# 02_POWER.net
KiCad netlist of a schematic drawn in Altium Designer
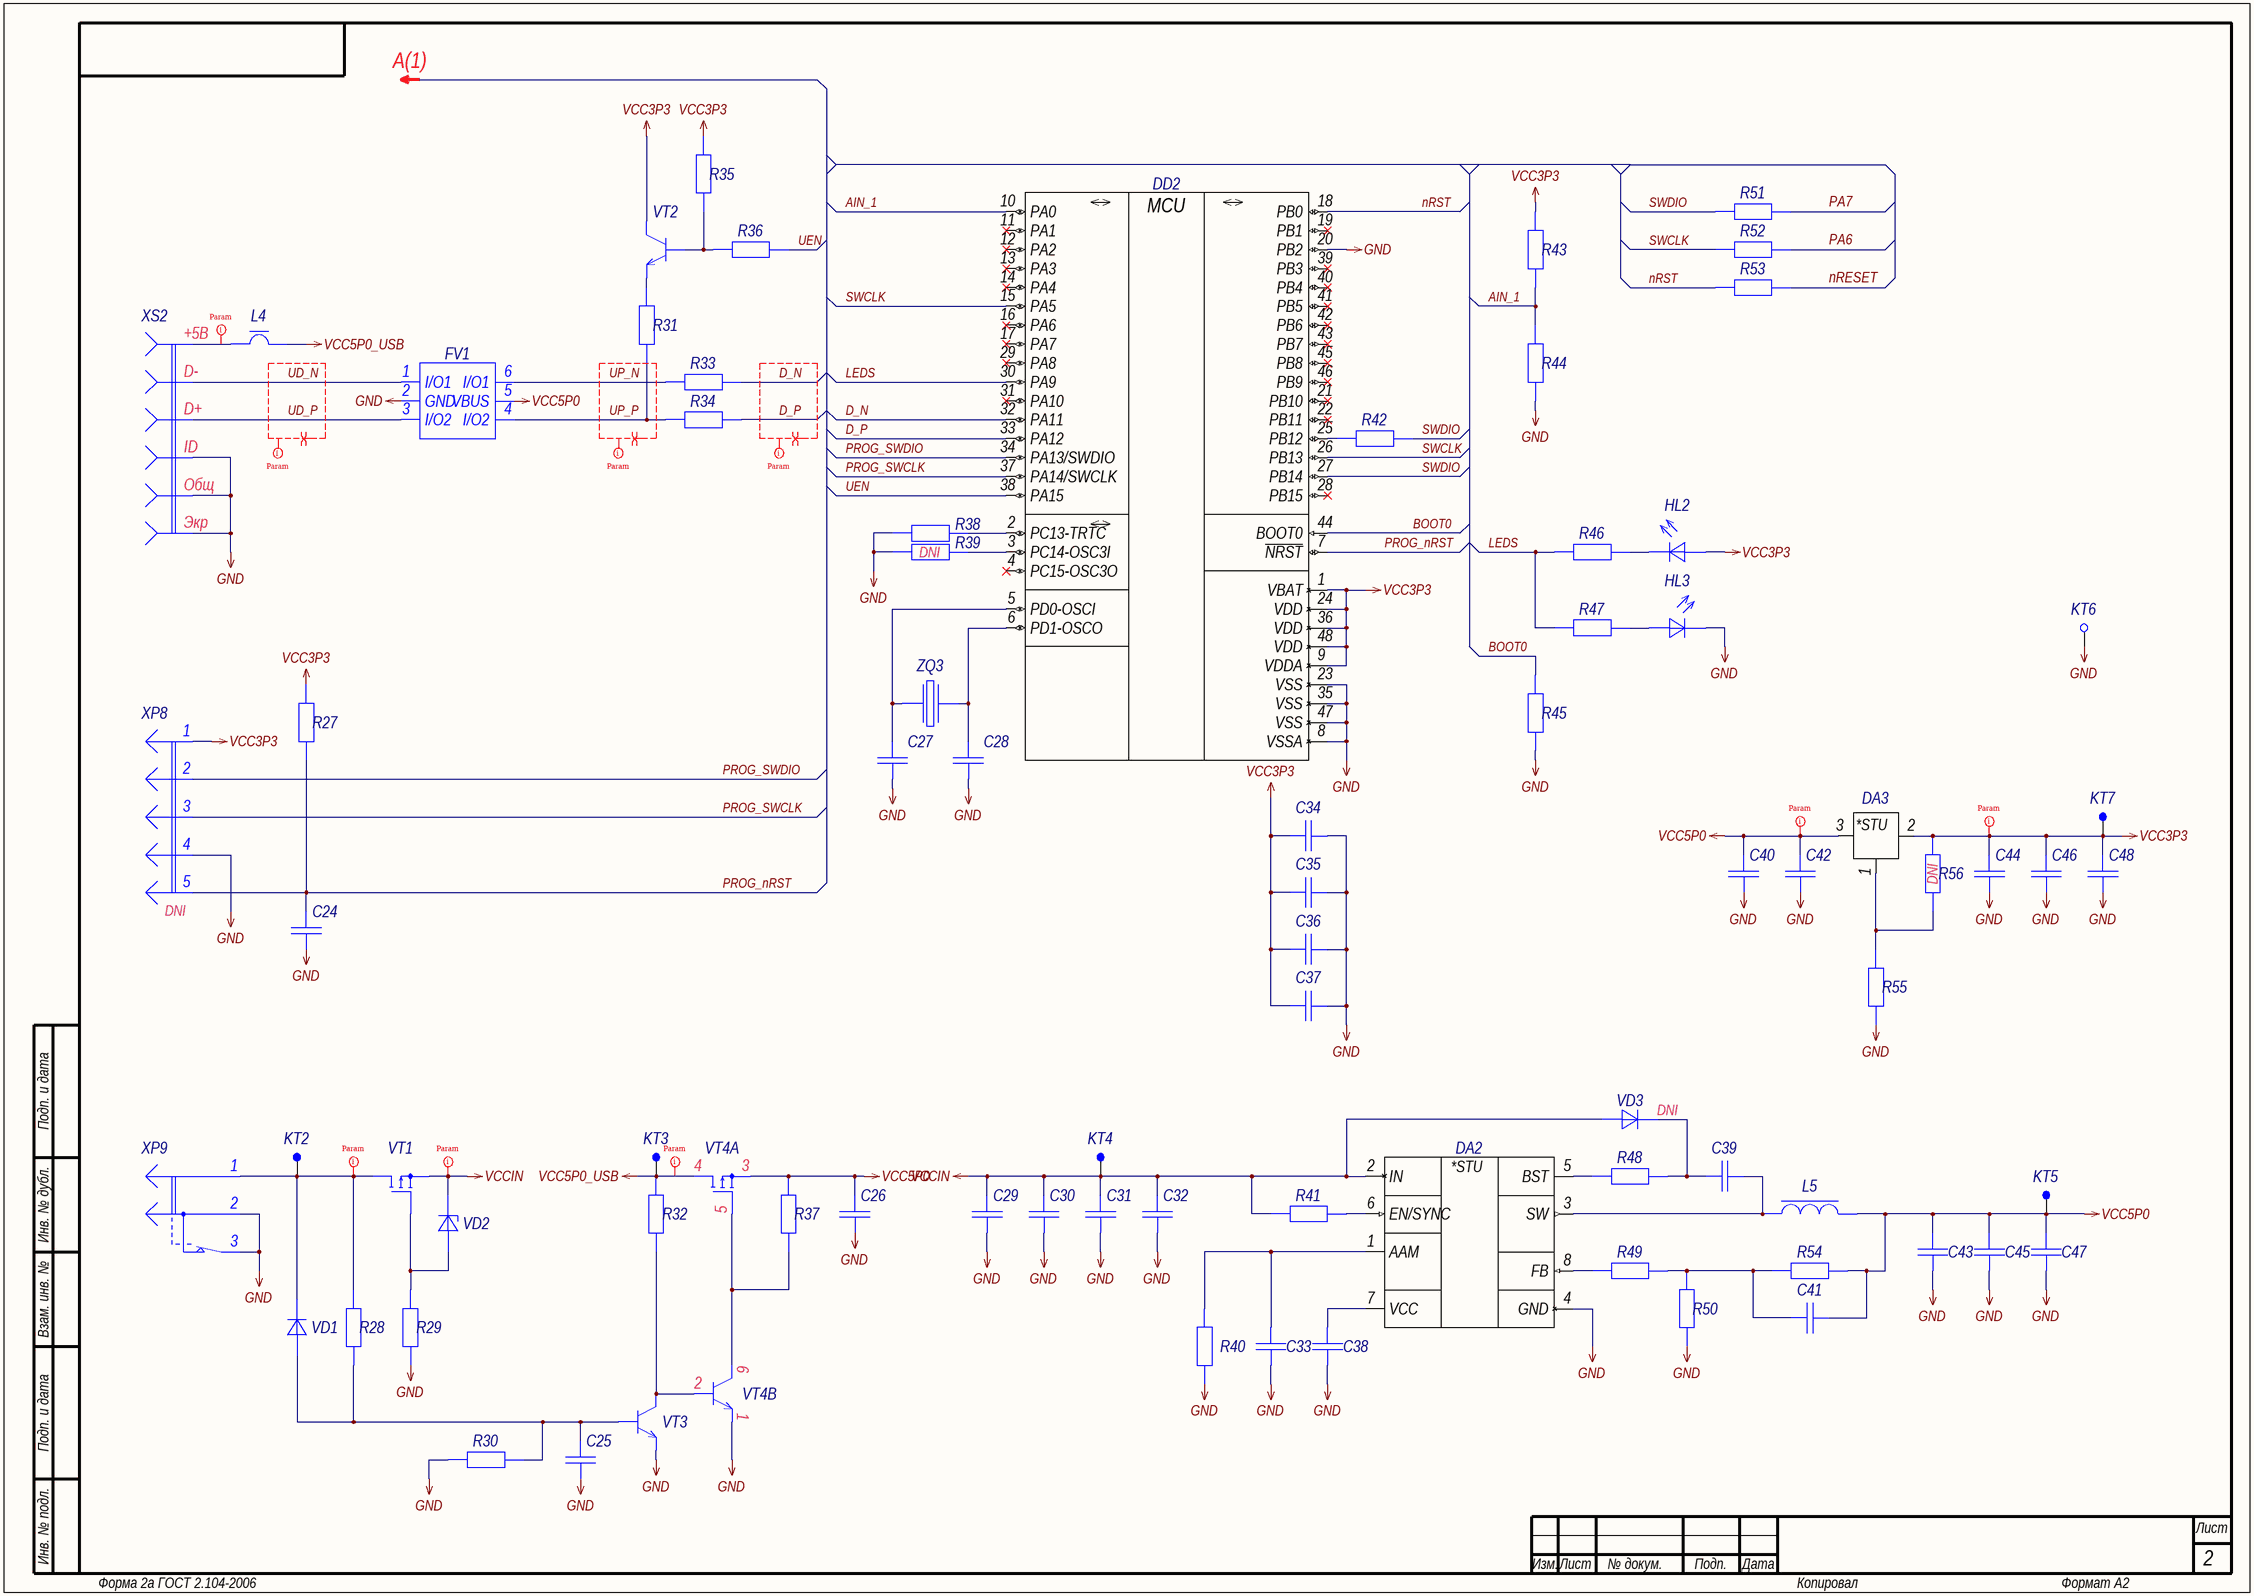
[diagram p0: 02_POWER.SchDoc]

(export (version "E")
  (design (tool "Eeschema 10.0.6"))
  (components
    (comp (ref "C24")
      (value "Capacitor")
      (footprint "C0603_L")
      (fields
        (field (name "PART NUMBER") "GRM188R72A104KA35D")
        (field (name "VOLTAGE") "100V")
        (field (name "TOLERANCE") "±10%")
        (field (name "PUBLISHER") "Andrew Danich")
      )
      (libsource (lib "ADLib") (part "Capacitor"))
    )
    (comp (ref "C25")
      (value "Capacitor")
      (footprint "C0603_L")
      (fields
        (field (name "PART NUMBER") "GRM188R72A104KA35D")
        (field (name "VOLTAGE") "100V")
        (field (name "TOLERANCE") "±10%")
        (field (name "PUBLISHER") "Andrew Danich")
      )
      (libsource (lib "ADLib") (part "Capacitor"))
    )
    (comp (ref "C26")
      (value "Capacitor")
      (footprint "C0805_L")
      (fields
        (field (name "PART NUMBER") "GRM21BR60J226ME39L")
        (field (name "VOLTAGE") "6.3V")
        (field (name "TOLERANCE") "±20%")
        (field (name "PUBLISHER") "Andrew Danich")
      )
      (libsource (lib "ADLib") (part "Capacitor"))
    )
    (comp (ref "C27")
      (value "Capacitor")
      (footprint "C0603_L")
      (fields
        (field (name "PART NUMBER") "GCM1885C1H150JA16D")
        (field (name "VOLTAGE") "50V")
        (field (name "TOLERANCE") "±5%")
        (field (name "PUBLISHER") "Andrew Danich")
      )
      (libsource (lib "ADLib") (part "Capacitor"))
    )
    (comp (ref "C28")
      (value "Capacitor")
      (footprint "C0603_L")
      (fields
        (field (name "PART NUMBER") "GCM1885C1H150JA16D")
        (field (name "VOLTAGE") "50V")
        (field (name "TOLERANCE") "±5%")
        (field (name "PUBLISHER") "Andrew Danich")
      )
      (libsource (lib "ADLib") (part "Capacitor"))
    )
    (comp (ref "C29")
      (value "Capacitor")
      (footprint "C1206_L")
      (fields
        (field (name "PART NUMBER") "GRM31CR71A226KE15L")
        (field (name "VOLTAGE") "10V")
        (field (name "TOLERANCE") "±10%")
        (field (name "PUBLISHER") "Andrew Danich")
      )
      (libsource (lib "ADLib") (part "Capacitor"))
    )
    (comp (ref "C30")
      (value "Capacitor")
      (footprint "C1206_L")
      (fields
        (field (name "PART NUMBER") "GRM31CR71A226KE15L")
        (field (name "VOLTAGE") "10V")
        (field (name "TOLERANCE") "±10%")
        (field (name "PUBLISHER") "Andrew Danich")
      )
      (libsource (lib "ADLib") (part "Capacitor"))
    )
    (comp (ref "C31")
      (value "Capacitor")
      (footprint "C1206_L")
      (fields
        (field (name "PART NUMBER") "GRM31CR71A226KE15L")
        (field (name "VOLTAGE") "10V")
        (field (name "TOLERANCE") "±10%")
        (field (name "PUBLISHER") "Andrew Danich")
      )
      (libsource (lib "ADLib") (part "Capacitor"))
    )
    (comp (ref "C32")
      (value "Capacitor")
      (footprint "C0603_L")
      (fields
        (field (name "PART NUMBER") "GRM188R72A104KA35D")
        (field (name "VOLTAGE") "100V")
        (field (name "TOLERANCE") "±10%")
        (field (name "PUBLISHER") "Andrew Danich")
      )
      (libsource (lib "ADLib") (part "Capacitor"))
    )
    (comp (ref "C33")
      (value "Capacitor")
      (footprint "C0603_L")
      (fields
        (field (name "PART NUMBER") "GRM1885C2A102JA01D")
        (field (name "VOLTAGE") "100V")
        (field (name "TOLERANCE") "±5%")
        (field (name "PUBLISHER") "Andrew Danich")
      )
      (libsource (lib "ADLib") (part "Capacitor"))
    )
    (comp (ref "C34")
      (value "Capacitor")
      (footprint "C0603_L")
      (fields
        (field (name "PART NUMBER") "GRM188R72A104KA35D")
        (field (name "VOLTAGE") "100V")
        (field (name "TOLERANCE") "±10%")
        (field (name "PUBLISHER") "Andrew Danich")
      )
      (libsource (lib "ADLib") (part "Capacitor"))
    )
    (comp (ref "C35")
      (value "Capacitor")
      (footprint "C0603_L")
      (fields
        (field (name "PART NUMBER") "GRM188R72A104KA35D")
        (field (name "VOLTAGE") "100V")
        (field (name "TOLERANCE") "±10%")
        (field (name "PUBLISHER") "Andrew Danich")
      )
      (libsource (lib "ADLib") (part "Capacitor"))
    )
    (comp (ref "C36")
      (value "Capacitor")
      (footprint "C0603_L")
      (fields
        (field (name "PART NUMBER") "GRM188R72A104KA35D")
        (field (name "VOLTAGE") "100V")
        (field (name "TOLERANCE") "±10%")
        (field (name "PUBLISHER") "Andrew Danich")
      )
      (libsource (lib "ADLib") (part "Capacitor"))
    )
    (comp (ref "C37")
      (value "Capacitor")
      (footprint "C0603_L")
      (fields
        (field (name "PART NUMBER") "GRM188R72A104KA35D")
        (field (name "VOLTAGE") "100V")
        (field (name "TOLERANCE") "±10%")
        (field (name "PUBLISHER") "Andrew Danich")
      )
      (libsource (lib "ADLib") (part "Capacitor"))
    )
    (comp (ref "C38")
      (value "Capacitor")
      (footprint "C0603_L")
      (fields
        (field (name "PART NUMBER") "GRM188R72A104KA35D")
        (field (name "VOLTAGE") "100V")
        (field (name "TOLERANCE") "±10%")
        (field (name "PUBLISHER") "Andrew Danich")
      )
      (libsource (lib "ADLib") (part "Capacitor"))
    )
    (comp (ref "C39")
      (value "Capacitor")
      (footprint "C0603_L")
      (fields
        (field (name "PART NUMBER") "GRM188R72A104KA35D")
        (field (name "VOLTAGE") "100V")
        (field (name "TOLERANCE") "±10%")
        (field (name "PUBLISHER") "Andrew Danich")
      )
      (libsource (lib "ADLib") (part "Capacitor"))
    )
    (comp (ref "C40")
      (value "Capacitor")
      (footprint "C0805_L")
      (fields
        (field (name "PART NUMBER") "GRM21BR60J226ME39L")
        (field (name "VOLTAGE") "6.3V")
        (field (name "TOLERANCE") "±20%")
        (field (name "PUBLISHER") "Andrew Danich")
      )
      (libsource (lib "ADLib") (part "Capacitor"))
    )
    (comp (ref "C41")
      (value "Capacitor")
      (footprint "C0603_L")
      (fields
        (field (name "PART NUMBER") "GRM1885C1H330JA01D")
        (field (name "VOLTAGE") "50V")
        (field (name "TOLERANCE") "±5%")
        (field (name "PUBLISHER") "Andrew Danich")
      )
      (libsource (lib "ADLib") (part "Capacitor"))
    )
    (comp (ref "C42")
      (value "Capacitor")
      (footprint "C0603_L")
      (fields
        (field (name "PART NUMBER") "GRM188R72A104KA35D")
        (field (name "VOLTAGE") "100V")
        (field (name "TOLERANCE") "±10%")
        (field (name "PUBLISHER") "Andrew Danich")
      )
      (libsource (lib "ADLib") (part "Capacitor"))
    )
    (comp (ref "C43")
      (value "Capacitor")
      (footprint "C0805_L")
      (fields
        (field (name "PART NUMBER") "GRM21BR60J226ME39L")
        (field (name "VOLTAGE") "6.3V")
        (field (name "TOLERANCE") "±20%")
        (field (name "PUBLISHER") "Andrew Danich")
      )
      (libsource (lib "ADLib") (part "Capacitor"))
    )
    (comp (ref "C44")
      (value "Capacitor")
      (footprint "C0603_L")
      (fields
        (field (name "PART NUMBER") "GRM188R72A104KA35D")
        (field (name "VOLTAGE") "100V")
        (field (name "TOLERANCE") "±10%")
        (field (name "PUBLISHER") "Andrew Danich")
      )
      (libsource (lib "ADLib") (part "Capacitor"))
    )
    (comp (ref "C45")
      (value "Capacitor")
      (footprint "C0805_L")
      (fields
        (field (name "PART NUMBER") "GRM21BR60J226ME39L")
        (field (name "VOLTAGE") "6.3V")
        (field (name "TOLERANCE") "±20%")
        (field (name "PUBLISHER") "Andrew Danich")
      )
      (libsource (lib "ADLib") (part "Capacitor"))
    )
    (comp (ref "C46")
      (value "Capacitor")
      (footprint "C0805_L")
      (fields
        (field (name "PART NUMBER") "GRM21BR60J226ME39L")
        (field (name "VOLTAGE") "6.3V")
        (field (name "TOLERANCE") "±20%")
        (field (name "PUBLISHER") "Andrew Danich")
      )
      (libsource (lib "ADLib") (part "Capacitor"))
    )
    (comp (ref "C47")
      (value "Capacitor")
      (footprint "C0805_L")
      (fields
        (field (name "PART NUMBER") "GRM21BR60J226ME39L")
        (field (name "VOLTAGE") "6.3V")
        (field (name "TOLERANCE") "±20%")
        (field (name "PUBLISHER") "Andrew Danich")
      )
      (libsource (lib "ADLib") (part "Capacitor"))
    )
    (comp (ref "C48")
      (value "Capacitor")
      (footprint "C0805_L")
      (fields
        (field (name "PART NUMBER") "GRM21BR60J226ME39L")
        (field (name "VOLTAGE") "6.3V")
        (field (name "TOLERANCE") "±20%")
        (field (name "PUBLISHER") "Andrew Danich")
      )
      (libsource (lib "ADLib") (part "Capacitor"))
    )
    (comp (ref "DA2")
      (value "MP2315GJ")
      (footprint "TSOT-23-8_065P290X160X100_N")
      (fields
        (field (name "PART NUMBER") "MP2315GJ-Z")
        (field (name "MANUFACTURER") "Monolithic Power Systems")
        (field (name "PUBLISHER") "Andrew Danich")
      )
      (libsource (lib "ADLib") (part "MP2315GJ"))
    )
    (comp (ref "DA3")
      (value "LM1117-Series")
      (footprint "SOT-223_230P650X350X180_N")
      (fields (field (name "PART NUMBER") "LM1117MPX-3.3") (field (name "PUBLISHER") "Andrew Danich"))
      (libsource (lib "ADLib") (part "LM1117-Series"))
    )
    (comp (ref "DD2")
      (value "STM32F103Cxxx-Series")
      (footprint "LQFP-48_050P700X700X160_N")
      (fields
        (field (name "PART NUMBER") "STM32F103C8T6")
        (field (name "MANUFACTURER") "STMicroelectronics")
        (field (name "PUBLISHER") "Andrew Danich")
      )
      (libsource (lib "ADLib") (part "STM32F103Cxxx-Series"))
    )
    (comp (ref "FV1")
      (value "USBLC6-2SC6")
      (footprint "SOT-23-6_095P290X160X145_N")
      (fields (field (name "MANUFACTURER") "STMicroelectronics") (field (name "PUBLISHER") "Andrew Danich"))
      (libsource (lib "ADLib") (part "USBLC6-2SC6"))
    )
    (comp (ref "HL2")
      (value "Text")
      (footprint "LD0603_L")
      (fields (field (name "PART NUMBER") "BL-LS0603GC") (field (name "PUBLISHER") "Andrew Danich"))
      (libsource (lib "ADLib") (part "Led-1"))
    )
    (comp (ref "HL3")
      (value "Text")
      (footprint "LD0603_L")
      (fields (field (name "PART NUMBER") "BL-LS0603HC") (field (name "PUBLISHER") "Andrew Danich"))
      (libsource (lib "ADLib") (part "Led-1"))
    )
    (comp (ref "KT2")
      (value "VCCIN")
      (footprint "TP-SMT-C-0.8mm")
      (fields (field (name "PART NUMBER") "TestPoint-SMT") (field (name "PUBLISHER") "Andrew Danich"))
      (libsource (lib "ADLib") (part "TP-S-1"))
    )
    (comp (ref "KT3")
      (value "VBUS")
      (footprint "TP-SMT-C-0.8mm")
      (fields (field (name "PART NUMBER") "TestPoint-SMT") (field (name "PUBLISHER") "Andrew Danich"))
      (libsource (lib "ADLib") (part "TP-S-1"))
    )
    (comp (ref "KT4")
      (value "VCCIN")
      (footprint "TP-SMT-C-0.8mm")
      (fields (field (name "PART NUMBER") "TestPoint-SMT") (field (name "PUBLISHER") "Andrew Danich"))
      (libsource (lib "ADLib") (part "TP-S-1"))
    )
    (comp (ref "KT5")
      (value "+5V")
      (footprint "TP-SMT-C-0.8mm")
      (fields (field (name "PART NUMBER") "TestPoint-SMT") (field (name "PUBLISHER") "Andrew Danich"))
      (libsource (lib "ADLib") (part "TP-S-1"))
    )
    (comp (ref "KT6")
      (value "ОБЩ")
      (footprint "5001")
      (fields
        (field (name "PART NUMBER") "5001")
        (field (name "MANUFACTURER") "Keystone Electronics")
        (field (name "PUBLISHER") "Andrew Danich")
      )
      (libsource (lib "ADLib") (part "TP-1"))
    )
    (comp (ref "KT7")
      (value "+3.3V")
      (footprint "TP-SMT-C-0.8mm")
      (fields (field (name "PART NUMBER") "TestPoint-SMT") (field (name "PUBLISHER") "Andrew Danich"))
      (libsource (lib "ADLib") (part "TP-S-1"))
    )
    (comp (ref "L4")
      (value "FerriteBead")
      (footprint "L0603_L")
      (fields
        (field (name "PART NUMBER") "BLM18PG331SN1")
        (field (name "TOLERANCE") "±25%")
        (field (name "MANUFACTURER") "Murata")
        (field (name "PUBLISHER") "Andrew Danich")
      )
      (libsource (lib "ADLib") (part "FerriteBead"))
    )
    (comp (ref "L5")
      (value "Coil")
      (footprint "SRP5030T-Series")
      (fields
        (field (name "PART NUMBER") "SRP5030T-4R7M")
        (field (name "TOLERANCE") "±20%")
        (field (name "MANUFACTURER") "Bourns")
        (field (name "PUBLISHER") "Andrew Danich")
      )
      (libsource (lib "ADLib") (part "Coil"))
    )
    (comp (ref "R27")
      (value "Resistor")
      (footprint "R0603_L")
      (fields
        (field (name "PART NUMBER") "RC0603JR-0710KL")
        (field (name "TOLERANCE") "±5%")
        (field (name "MANUFACTURER") "Yageo")
        (field (name "PUBLISHER") "Andrew Danich")
      )
      (libsource (lib "ADLib") (part "Resistor"))
    )
    (comp (ref "R28")
      (value "Resistor")
      (footprint "R0603_L")
      (fields
        (field (name "PART NUMBER") "RC0603JR-0710KL")
        (field (name "TOLERANCE") "±5%")
        (field (name "MANUFACTURER") "Yageo")
        (field (name "PUBLISHER") "Andrew Danich")
      )
      (libsource (lib "ADLib") (part "Resistor"))
    )
    (comp (ref "R29")
      (value "Resistor")
      (footprint "R0603_L")
      (fields
        (field (name "PART NUMBER") "RC0603JR-0710KL")
        (field (name "TOLERANCE") "±5%")
        (field (name "MANUFACTURER") "Yageo")
        (field (name "PUBLISHER") "Andrew Danich")
      )
      (libsource (lib "ADLib") (part "Resistor"))
    )
    (comp (ref "R30")
      (value "Resistor")
      (footprint "R0603_L")
      (fields
        (field (name "PART NUMBER") "RC0603JR-0710KL")
        (field (name "TOLERANCE") "±5%")
        (field (name "MANUFACTURER") "Yageo")
        (field (name "PUBLISHER") "Andrew Danich")
      )
      (libsource (lib "ADLib") (part "Resistor"))
    )
    (comp (ref "R31")
      (value "Resistor")
      (footprint "R0603_L")
      (fields
        (field (name "PART NUMBER") "RC0603JR-071K5L")
        (field (name "TOLERANCE") "±5%")
        (field (name "MANUFACTURER") "Yageo")
        (field (name "PUBLISHER") "Andrew Danich")
      )
      (libsource (lib "ADLib") (part "Resistor"))
    )
    (comp (ref "R32")
      (value "Resistor")
      (footprint "R0603_L")
      (fields
        (field (name "PART NUMBER") "RC0603JR-0710KL")
        (field (name "TOLERANCE") "±5%")
        (field (name "MANUFACTURER") "Yageo")
        (field (name "PUBLISHER") "Andrew Danich")
      )
      (libsource (lib "ADLib") (part "Resistor"))
    )
    (comp (ref "R33")
      (value "Resistor")
      (footprint "R0603_L")
      (fields
        (field (name "PART NUMBER") "RC0603JR-0722RL")
        (field (name "TOLERANCE") "±5%")
        (field (name "MANUFACTURER") "Yageo")
        (field (name "PUBLISHER") "Andrew Danich")
      )
      (libsource (lib "ADLib") (part "Resistor"))
    )
    (comp (ref "R34")
      (value "Resistor")
      (footprint "R0603_L")
      (fields
        (field (name "PART NUMBER") "RC0603JR-0722RL")
        (field (name "TOLERANCE") "±5%")
        (field (name "MANUFACTURER") "Yageo")
        (field (name "PUBLISHER") "Andrew Danich")
      )
      (libsource (lib "ADLib") (part "Resistor"))
    )
    (comp (ref "R35")
      (value "Resistor")
      (footprint "R0603_L")
      (fields
        (field (name "PART NUMBER") "RC0603JR-074K7L")
        (field (name "TOLERANCE") "±5%")
        (field (name "MANUFACTURER") "Yageo")
        (field (name "PUBLISHER") "Andrew Danich")
      )
      (libsource (lib "ADLib") (part "Resistor"))
    )
    (comp (ref "R36")
      (value "Resistor")
      (footprint "R0603_L")
      (fields
        (field (name "PART NUMBER") "RC0603JR-07100R")
        (field (name "TOLERANCE") "±5%")
        (field (name "MANUFACTURER") "Yageo")
        (field (name "PUBLISHER") "Andrew Danich")
      )
      (libsource (lib "ADLib") (part "Resistor"))
    )
    (comp (ref "R37")
      (value "Resistor")
      (footprint "R0603_L")
      (fields
        (field (name "PART NUMBER") "RC0603JR-0710KL")
        (field (name "TOLERANCE") "±5%")
        (field (name "MANUFACTURER") "Yageo")
        (field (name "PUBLISHER") "Andrew Danich")
      )
      (libsource (lib "ADLib") (part "Resistor"))
    )
    (comp (ref "R38")
      (value "Resistor")
      (footprint "R0603_L")
      (fields
        (field (name "PART NUMBER") "RC0603JR-0710KL")
        (field (name "TOLERANCE") "±5%")
        (field (name "MANUFACTURER") "Yageo")
        (field (name "PUBLISHER") "Andrew Danich")
      )
      (libsource (lib "ADLib") (part "Resistor"))
    )
    (comp (ref "R39")
      (value "Resistor")
      (footprint "R0603_L")
      (fields
        (field (name "PART NUMBER") "RC0603JR-0710KL")
        (field (name "TOLERANCE") "±5%")
        (field (name "MANUFACTURER") "Yageo")
        (field (name "PUBLISHER") "Andrew Danich")
      )
      (libsource (lib "ADLib") (part "Resistor"))
    )
    (comp (ref "R40")
      (value "Resistor")
      (footprint "R0603_L")
      (fields
        (field (name "PART NUMBER") "RC0603FR-0763K4L")
        (field (name "TOLERANCE") "±1%")
        (field (name "MANUFACTURER") "Yageo")
        (field (name "PUBLISHER") "Andrew Danich")
      )
      (libsource (lib "ADLib") (part "Resistor"))
    )
    (comp (ref "R41")
      (value "Resistor")
      (footprint "R0603_L")
      (fields
        (field (name "PART NUMBER") "RC0603JR-07100KL")
        (field (name "TOLERANCE") "±5%")
        (field (name "MANUFACTURER") "Yageo")
        (field (name "PUBLISHER") "Andrew Danich")
      )
      (libsource (lib "ADLib") (part "Resistor"))
    )
    (comp (ref "R42")
      (value "Resistor")
      (footprint "R0603_L")
      (fields
        (field (name "PART NUMBER") "RC0603JR-07100R")
        (field (name "TOLERANCE") "±5%")
        (field (name "MANUFACTURER") "Yageo")
        (field (name "PUBLISHER") "Andrew Danich")
      )
      (libsource (lib "ADLib") (part "Resistor"))
    )
    (comp (ref "R43")
      (value "Resistor")
      (footprint "R0603_L")
      (fields
        (field (name "PART NUMBER") "RC0603JR-074K7L")
        (field (name "TOLERANCE") "±5%")
        (field (name "MANUFACTURER") "Yageo")
        (field (name "PUBLISHER") "Andrew Danich")
      )
      (libsource (lib "ADLib") (part "Resistor"))
    )
    (comp (ref "R44")
      (value "Resistor")
      (footprint "R0603_L")
      (fields
        (field (name "PART NUMBER") "RC0603JR-074K7L")
        (field (name "TOLERANCE") "±5%")
        (field (name "MANUFACTURER") "Yageo")
        (field (name "PUBLISHER") "Andrew Danich")
      )
      (libsource (lib "ADLib") (part "Resistor"))
    )
    (comp (ref "R45")
      (value "Resistor")
      (footprint "R0603_L")
      (fields
        (field (name "PART NUMBER") "RC0603JR-0710KL")
        (field (name "TOLERANCE") "±5%")
        (field (name "MANUFACTURER") "Yageo")
        (field (name "PUBLISHER") "Andrew Danich")
      )
      (libsource (lib "ADLib") (part "Resistor"))
    )
    (comp (ref "R46")
      (value "Resistor")
      (footprint "R0603_L")
      (fields
        (field (name "PART NUMBER") "RC0603JR-07330RL")
        (field (name "TOLERANCE") "±5%")
        (field (name "MANUFACTURER") "Yageo")
        (field (name "PUBLISHER") "Andrew Danich")
      )
      (libsource (lib "ADLib") (part "Resistor"))
    )
    (comp (ref "R47")
      (value "Resistor")
      (footprint "R0603_L")
      (fields
        (field (name "PART NUMBER") "RC0603JR-07330RL")
        (field (name "TOLERANCE") "±5%")
        (field (name "MANUFACTURER") "Yageo")
        (field (name "PUBLISHER") "Andrew Danich")
      )
      (libsource (lib "ADLib") (part "Resistor"))
    )
    (comp (ref "R48")
      (value "Resistor")
      (footprint "R0603_L")
      (fields
        (field (name "PART NUMBER") "RC0603JR-0720RL")
        (field (name "TOLERANCE") "±5%")
        (field (name "MANUFACTURER") "Yageo")
        (field (name "PUBLISHER") "Andrew Danich")
      )
      (libsource (lib "ADLib") (part "Resistor"))
    )
    (comp (ref "R49")
      (value "Resistor")
      (footprint "R0603_L")
      (fields
        (field (name "PART NUMBER") "RC0603JR-0733KL")
        (field (name "TOLERANCE") "±5%")
        (field (name "MANUFACTURER") "Yageo")
        (field (name "PUBLISHER") "Andrew Danich")
      )
      (libsource (lib "ADLib") (part "Resistor"))
    )
    (comp (ref "R50")
      (value "Resistor")
      (footprint "R0603_L")
      (fields
        (field (name "PART NUMBER") "RC0603JR-076K8L")
        (field (name "TOLERANCE") "±5%")
        (field (name "MANUFACTURER") "Yageo")
        (field (name "PUBLISHER") "Andrew Danich")
      )
      (libsource (lib "ADLib") (part "Resistor"))
    )
    (comp (ref "R51")
      (value "Resistor")
      (footprint "R0603_L")
      (fields
        (field (name "PART NUMBER") "RC0603JR-0722RL")
        (field (name "TOLERANCE") "±5%")
        (field (name "MANUFACTURER") "Yageo")
        (field (name "PUBLISHER") "Andrew Danich")
      )
      (libsource (lib "ADLib") (part "Resistor"))
    )
    (comp (ref "R52")
      (value "Resistor")
      (footprint "R0603_L")
      (fields
        (field (name "PART NUMBER") "RC0603JR-0722RL")
        (field (name "TOLERANCE") "±5%")
        (field (name "MANUFACTURER") "Yageo")
        (field (name "PUBLISHER") "Andrew Danich")
      )
      (libsource (lib "ADLib") (part "Resistor"))
    )
    (comp (ref "R53")
      (value "Resistor")
      (footprint "R0603_L")
      (fields
        (field (name "PART NUMBER") "RC0603JR-0722RL")
        (field (name "TOLERANCE") "±5%")
        (field (name "MANUFACTURER") "Yageo")
        (field (name "PUBLISHER") "Andrew Danich")
      )
      (libsource (lib "ADLib") (part "Resistor"))
    )
    (comp (ref "R54")
      (value "Resistor")
      (footprint "R0603_L")
      (fields
        (field (name "PART NUMBER") "RC0603JR-0736KL")
        (field (name "TOLERANCE") "±5%")
        (field (name "MANUFACTURER") "Yageo")
        (field (name "PUBLISHER") "Andrew Danich")
      )
      (libsource (lib "ADLib") (part "Resistor"))
    )
    (comp (ref "R55")
      (value "Resistor")
      (footprint "R0603_L")
      (fields
        (field (name "PART NUMBER") "RC0603JR-070R")
        (field (name "TOLERANCE") "±5%")
        (field (name "MANUFACTURER") "Yageo")
        (field (name "PUBLISHER") "Andrew Danich")
      )
      (libsource (lib "ADLib") (part "Resistor"))
    )
    (comp (ref "R56")
      (value "Resistor")
      (footprint "R0603_L")
      (fields
        (field (name "PART NUMBER") "RC0603JR-070R")
        (field (name "TOLERANCE") "±5%")
        (field (name "MANUFACTURER") "Yageo")
        (field (name "PUBLISHER") "Andrew Danich")
      )
      (libsource (lib "ADLib") (part "Resistor"))
    )
    (comp (ref "VD1")
      (value "Diode")
      (footprint "SOD-323")
      (fields
        (field (name "PART NUMBER") "1N4148WS-7-F")
        (field (name "MANUFACTURER") "Diodes Incorporated")
        (field (name "PUBLISHER") "Andrew Danich")
      )
      (libsource (lib "ADLib") (part "Diode"))
    )
    (comp (ref "VD2")
      (value "Zener")
      (footprint "SOD-323")
      (fields
        (field (name "PART NUMBER") "BZX384-C12")
        (field (name "MANUFACTURER") "NXP")
        (field (name "PUBLISHER") "Andrew Danich")
      )
      (libsource (lib "ADLib") (part "Zener"))
    )
    (comp (ref "VD3")
      (value "Diode")
      (footprint "SOD-323")
      (fields
        (field (name "PART NUMBER") "1N4148WS-7-F")
        (field (name "MANUFACTURER") "Diodes Incorporated")
        (field (name "PUBLISHER") "Andrew Danich")
      )
      (libsource (lib "ADLib") (part "Diode"))
    )
    (comp (ref "VT1")
      (value "MOSFET-P")
      (footprint "SOT-23_190P290X160X145_N")
      (fields
        (field (name "PART NUMBER") "IRLML9301TRPBF")
        (field (name "MANUFACTURER") "International Rectifier")
        (field (name "PUBLISHER") "Andrew Danich")
      )
      (libsource (lib "ADLib") (part "MOSFET-P"))
    )
    (comp (ref "VT2")
      (value "BJT-NPN")
      (footprint "SOT-23_190P290X160X145_N")
      (fields (field (name "PART NUMBER") "BC847") (field (name "PUBLISHER") "Andrew Danich"))
      (libsource (lib "ADLib") (part "BJT-NPN"))
    )
    (comp (ref "VT3")
      (value "BJT-NPN")
      (footprint "SOT-23_190P290X160X145_N")
      (fields (field (name "PART NUMBER") "BC847") (field (name "PUBLISHER") "Andrew Danich"))
      (libsource (lib "ADLib") (part "BJT-NPN"))
    )
    (comp (ref "VT4")
      (value "PMC85XP")
      (footprint "SOT-1118-2M_065P200X200X065_N")
      (fields (field (name "MANUFACTURER") "NXP Semiconductors") (field (name "PUBLISHER") "Andrew Danich"))
      (libsource (lib "ADLib") (part "PMC85XP"))
    )
    (comp (ref "XP8")
      (value "Prog")
      (footprint "PLS-5")
      (fields (field (name "PART NUMBER") "PLS-5") (field (name "PUBLISHER") "Andrew Danich"))
      (libsource (lib "ADLib") (part "Con-5-M"))
    )
    (comp (ref "XP9")
      (value "DC")
      (footprint "DJK-02-Series")
      (fields
        (field (name "PART NUMBER") "DJK-02A")
        (field (name "MANUFACTURER") "JIA YI")
        (field (name "PUBLISHER") "Andrew Danich")
      )
      (libsource (lib "ADLib") (part "Con-2-M-DP"))
    )
    (comp (ref "XS2")
      (value "J-Link")
      (footprint "1981568-1")
      (fields
        (field (name "PART NUMBER") "1981568-1")
        (field (name "MANUFACTURER") "TE Connectivity")
        (field (name "PUBLISHER") "Andrew Danich")
      )
      (libsource (lib "ADLib") (part "Con-6-F-USB"))
    )
    (comp (ref "ZQ3")
      (value "Crystal")
      (footprint "SMD 5x3.2mm")
      (fields
        (field (name "PART NUMBER") "KX-9A 8.0 MHz 30/50/100 16 pF")
        (field (name "MANUFACTURER") "Geyer")
        (field (name "PUBLISHER") "Andrew Danich")
      )
      (libsource (lib "ADLib") (part "Crystal"))
    )
  )
  (nets
    (net (code "1") (name "/AIN_1") (class "Default")
      (node (ref "DD2") (pin "10") (pinfunction "PA0_10") (pintype "bidirectional"))
      (node (ref "R43") (pin "1") (pinfunction "1_1") (pintype "passive"))
      (node (ref "R44") (pin "2") (pinfunction "2_2") (pintype "passive"))
    )
    (net (code "2") (name "/BOOT0") (class "Default")
      (node (ref "DD2") (pin "44") (pinfunction "BOOT0_44") (pintype "input"))
      (node (ref "R45") (pin "2") (pinfunction "2_2") (pintype "passive"))
    )
    (net (code "3") (name "/D_N") (class "Default")
      (node (ref "DD2") (pin "32") (pinfunction "PA11_32") (pintype "bidirectional"))
      (node (ref "R33") (pin "2") (pinfunction "2_2") (pintype "passive"))
    )
    (net (code "4") (name "/D_P") (class "Default")
      (node (ref "DD2") (pin "33") (pinfunction "PA12_33") (pintype "bidirectional"))
      (node (ref "R34") (pin "2") (pinfunction "2_2") (pintype "passive"))
    )
    (net (code "5") (name "/LEDS") (class "Default")
      (node (ref "DD2") (pin "30") (pinfunction "PA9_30") (pintype "bidirectional"))
      (node (ref "R46") (pin "1") (pinfunction "1_1") (pintype "passive"))
      (node (ref "R47") (pin "1") (pinfunction "1_1") (pintype "passive"))
    )
    (net (code "6") (name "/PA6") (class "Default")
      (node (ref "R52") (pin "2") (pinfunction "2_2") (pintype "passive"))
    )
    (net (code "7") (name "/PA7") (class "Default")
      (node (ref "R51") (pin "2") (pinfunction "2_2") (pintype "passive"))
    )
    (net (code "8") (name "/PROG_SWCLK") (class "Default")
      (node (ref "DD2") (pin "37") (pinfunction "PA14/SWCLK_37") (pintype "bidirectional"))
      (node (ref "XP8") (pin "3") (pintype "passive"))
    )
    (net (code "9") (name "/PROG_SWDIO") (class "Default")
      (node (ref "DD2") (pin "34") (pinfunction "PA13/SWDIO_34") (pintype "bidirectional"))
      (node (ref "XP8") (pin "2") (pintype "passive"))
    )
    (net (code "10") (name "/PROG_nRST") (class "Default")
      (node (ref "C24") (pin "2") (pinfunction "2_2") (pintype "passive"))
      (node (ref "DD2") (pin "7") (pinfunction "~{NRST}_7") (pintype "bidirectional"))
      (node (ref "R27") (pin "1") (pinfunction "1_1") (pintype "passive"))
      (node (ref "XP8") (pin "5") (pintype "passive"))
    )
    (net (code "11") (name "/SWCLK") (class "Default")
      (node (ref "DD2") (pin "15") (pinfunction "PA5_15") (pintype "bidirectional"))
      (node (ref "DD2") (pin "26") (pinfunction "PB13_26") (pintype "bidirectional"))
      (node (ref "R52") (pin "1") (pinfunction "1_1") (pintype "passive"))
    )
    (net (code "12") (name "/SWDIO") (class "Default")
      (node (ref "DD2") (pin "27") (pinfunction "PB14_27") (pintype "bidirectional"))
      (node (ref "R42") (pin "2") (pinfunction "2_2") (pintype "passive"))
      (node (ref "R51") (pin "1") (pinfunction "1_1") (pintype "passive"))
    )
    (net (code "13") (name "/UD_N") (class "Default")
      (node (ref "FV1") (pin "1") (pinfunction "I/O1_1") (pintype "passive"))
      (node (ref "XS2") (pin "2") (pintype "passive"))
    )
    (net (code "14") (name "/UD_P") (class "Default")
      (node (ref "FV1") (pin "3") (pinfunction "I/O2_3") (pintype "passive"))
      (node (ref "XS2") (pin "3") (pintype "passive"))
    )
    (net (code "15") (name "/UEN") (class "Default")
      (node (ref "DD2") (pin "38") (pinfunction "PA15_38") (pintype "bidirectional"))
      (node (ref "R36") (pin "2") (pinfunction "2_2") (pintype "passive"))
    )
    (net (code "16") (name "/UP_N") (class "Default")
      (node (ref "FV1") (pin "6") (pinfunction "I/O1_6") (pintype "passive"))
      (node (ref "R33") (pin "1") (pinfunction "1_1") (pintype "passive"))
    )
    (net (code "17") (name "/UP_P") (class "Default")
      (node (ref "FV1") (pin "4") (pinfunction "I/O2_4") (pintype "passive"))
      (node (ref "R31") (pin "1") (pinfunction "1_1") (pintype "passive"))
      (node (ref "R34") (pin "1") (pinfunction "1_1") (pintype "passive"))
    )
    (net (code "18") (name "/nRESET") (class "Default")
      (node (ref "R53") (pin "2") (pinfunction "2_2") (pintype "passive"))
    )
    (net (code "19") (name "/nRST") (class "Default")
      (node (ref "DD2") (pin "18") (pinfunction "PB0_18") (pintype "bidirectional"))
      (node (ref "R53") (pin "1") (pinfunction "1_1") (pintype "passive"))
    )
    (net (code "20") (name "GND") (class "Default")
      (node (ref "C24") (pin "1") (pinfunction "1_1") (pintype "passive"))
      (node (ref "C25") (pin "1") (pinfunction "1_1") (pintype "passive"))
      (node (ref "C26") (pin "1") (pinfunction "1_1") (pintype "passive"))
      (node (ref "C27") (pin "1") (pinfunction "1_1") (pintype "passive"))
      (node (ref "C28") (pin "1") (pinfunction "1_1") (pintype "passive"))
      (node (ref "C29") (pin "1") (pinfunction "1_1") (pintype "passive"))
      (node (ref "C30") (pin "1") (pinfunction "1_1") (pintype "passive"))
      (node (ref "C31") (pin "1") (pinfunction "1_1") (pintype "passive"))
      (node (ref "C32") (pin "1") (pinfunction "1_1") (pintype "passive"))
      (node (ref "C33") (pin "1") (pinfunction "1_1") (pintype "passive"))
      (node (ref "C34") (pin "1") (pinfunction "1_1") (pintype "passive"))
      (node (ref "C35") (pin "1") (pinfunction "1_1") (pintype "passive"))
      (node (ref "C36") (pin "1") (pinfunction "1_1") (pintype "passive"))
      (node (ref "C37") (pin "1") (pinfunction "1_1") (pintype "passive"))
      (node (ref "C38") (pin "1") (pinfunction "1_1") (pintype "passive"))
      (node (ref "C40") (pin "1") (pinfunction "1_1") (pintype "passive"))
      (node (ref "C42") (pin "1") (pinfunction "1_1") (pintype "passive"))
      (node (ref "C43") (pin "1") (pinfunction "1_1") (pintype "passive"))
      (node (ref "C44") (pin "1") (pinfunction "1_1") (pintype "passive"))
      (node (ref "C45") (pin "1") (pinfunction "1_1") (pintype "passive"))
      (node (ref "C46") (pin "1") (pinfunction "1_1") (pintype "passive"))
      (node (ref "C47") (pin "1") (pinfunction "1_1") (pintype "passive"))
      (node (ref "C48") (pin "1") (pinfunction "1_1") (pintype "passive"))
      (node (ref "DA2") (pin "4") (pinfunction "GND_4") (pintype "power_in"))
      (node (ref "DD2") (pin "20") (pinfunction "PB2_20") (pintype "bidirectional"))
      (node (ref "DD2") (pin "23") (pinfunction "VSS_23") (pintype "power_in"))
      (node (ref "DD2") (pin "35") (pinfunction "VSS_35") (pintype "power_in"))
      (node (ref "DD2") (pin "47") (pinfunction "VSS_47") (pintype "power_in"))
      (node (ref "DD2") (pin "8") (pinfunction "VSSA_8") (pintype "power_in"))
      (node (ref "FV1") (pin "2") (pinfunction "GND_2") (pintype "passive"))
      (node (ref "HL3") (pin "2") (pinfunction "К_2") (pintype "passive"))
      (node (ref "KT6") (pin "1") (pinfunction "1_1") (pintype "passive"))
      (node (ref "R29") (pin "1") (pinfunction "1_1") (pintype "passive"))
      (node (ref "R30") (pin "2") (pinfunction "2_2") (pintype "passive"))
      (node (ref "R38") (pin "2") (pinfunction "2_2") (pintype "passive"))
      (node (ref "R39") (pin "2") (pinfunction "2_2") (pintype "passive"))
      (node (ref "R40") (pin "1") (pinfunction "1_1") (pintype "passive"))
      (node (ref "R44") (pin "1") (pinfunction "1_1") (pintype "passive"))
      (node (ref "R45") (pin "1") (pinfunction "1_1") (pintype "passive"))
      (node (ref "R50") (pin "1") (pinfunction "1_1") (pintype "passive"))
      (node (ref "R55") (pin "1") (pinfunction "1_1") (pintype "passive"))
      (node (ref "VT3") (pin "3") (pinfunction "Э_3") (pintype "passive"))
      (node (ref "VT4") (pin "1") (pinfunction "Э_1") (pintype "passive"))
      (node (ref "XP8") (pin "4") (pintype "passive"))
      (node (ref "XP9") (pin "2") (pintype "passive"))
      (node (ref "XP9") (pin "3") (pintype "passive"))
      (node (ref "XS2") (pin "4") (pintype "passive"))
      (node (ref "XS2") (pin "5") (pintype "passive"))
      (node (ref "XS2") (pin "6") (pintype "passive"))
    )
    (net (code "21") (name "Net-(C41-Pad1)") (class "Default")
      (node (ref "C41") (pin "1") (pinfunction "1_1") (pintype "passive"))
      (node (ref "R49") (pin "2") (pinfunction "2_2") (pintype "passive"))
      (node (ref "R50") (pin "2") (pinfunction "2_2") (pintype "passive"))
      (node (ref "R54") (pin "1") (pinfunction "1_1") (pintype "passive"))
    )
    (net (code "22") (name "Net-(DA2-AAM)") (class "Default")
      (node (ref "C33") (pin "2") (pinfunction "2_2") (pintype "passive"))
      (node (ref "DA2") (pin "1") (pinfunction "AAM_1") (pintype "passive"))
      (node (ref "R40") (pin "2") (pinfunction "2_2") (pintype "passive"))
    )
    (net (code "23") (name "Net-(DA2-BST)") (class "Default")
      (node (ref "DA2") (pin "5") (pinfunction "BST_5") (pintype "passive"))
      (node (ref "R48") (pin "1") (pinfunction "1_1") (pintype "passive"))
    )
    (net (code "24") (name "Net-(DA2-EN{slash}SYNC)") (class "Default")
      (node (ref "DA2") (pin "6") (pinfunction "EN/SYNC_6") (pintype "input"))
      (node (ref "R41") (pin "2") (pinfunction "2_2") (pintype "passive"))
    )
    (net (code "25") (name "Net-(DA2-FB)") (class "Default")
      (node (ref "DA2") (pin "8") (pinfunction "FB_8") (pintype "input"))
      (node (ref "R49") (pin "1") (pinfunction "1_1") (pintype "passive"))
    )
    (net (code "26") (name "Net-(DA2-SW)") (class "Default")
      (node (ref "C39") (pin "2") (pinfunction "2_2") (pintype "passive"))
      (node (ref "DA2") (pin "3") (pinfunction "SW_3") (pintype "output"))
      (node (ref "L5") (pin "1") (pinfunction "1_1") (pintype "passive"))
    )
    (net (code "27") (name "Net-(DA2-VCC)") (class "Default")
      (node (ref "C38") (pin "2") (pinfunction "2_2") (pintype "passive"))
      (node (ref "DA2") (pin "7") (pinfunction "VCC_7") (pintype "power_in"))
    )
    (net (code "28") (name "Net-(DA3-Adj{slash}GND)") (class "Default")
      (node (ref "DA3") (pin "1") (pinfunction "Adj/GND_1") (pintype "passive"))
      (node (ref "R55") (pin "2") (pinfunction "2_2") (pintype "passive"))
      (node (ref "R56") (pin "1") (pinfunction "1_1") (pintype "passive"))
    )
    (net (code "29") (name "Net-(DD2-PB12)") (class "Default")
      (node (ref "DD2") (pin "25") (pinfunction "PB12_25") (pintype "bidirectional"))
      (node (ref "R42") (pin "1") (pinfunction "1_1") (pintype "passive"))
    )
    (net (code "30") (name "Net-(DD2-PC13-TRTC)") (class "Default")
      (node (ref "DD2") (pin "2") (pinfunction "PC13-TRTC_2") (pintype "bidirectional"))
      (node (ref "R38") (pin "1") (pinfunction "1_1") (pintype "passive"))
    )
    (net (code "31") (name "Net-(DD2-PC14-OSC3I)") (class "Default")
      (node (ref "DD2") (pin "3") (pinfunction "PC14-OSC3I_3") (pintype "bidirectional"))
      (node (ref "R39") (pin "1") (pinfunction "1_1") (pintype "passive"))
    )
    (net (code "32") (name "Net-(DD2-PD0-OSCI)") (class "Default")
      (node (ref "C27") (pin "2") (pinfunction "2_2") (pintype "passive"))
      (node (ref "DD2") (pin "5") (pinfunction "PD0-OSCI_5") (pintype "bidirectional"))
      (node (ref "ZQ3") (pin "3") (pinfunction "3_3") (pintype "passive"))
    )
    (net (code "33") (name "Net-(DD2-PD1-OSCO)") (class "Default")
      (node (ref "C28") (pin "2") (pinfunction "2_2") (pintype "passive"))
      (node (ref "DD2") (pin "6") (pinfunction "PD1-OSCO_6") (pintype "bidirectional"))
      (node (ref "ZQ3") (pin "1") (pinfunction "1_1") (pintype "passive"))
    )
    (net (code "34") (name "Net-(HL2-К)") (class "Default")
      (node (ref "HL2") (pin "2") (pinfunction "К_2") (pintype "passive"))
      (node (ref "R46") (pin "2") (pinfunction "2_2") (pintype "passive"))
    )
    (net (code "35") (name "Net-(HL3-А)") (class "Default")
      (node (ref "HL3") (pin "1") (pinfunction "А_1") (pintype "passive"))
      (node (ref "R47") (pin "2") (pinfunction "2_2") (pintype "passive"))
    )
    (net (code "36") (name "Net-(L4-Pad1)") (class "Default")
      (node (ref "L4") (pin "1") (pinfunction "1_1") (pintype "passive"))
      (node (ref "XS2") (pin "1") (pintype "passive"))
    )
    (net (code "37") (name "Net-(VD1-А)") (class "Default")
      (node (ref "C25") (pin "2") (pinfunction "2_2") (pintype "passive"))
      (node (ref "R28") (pin "1") (pinfunction "1_1") (pintype "passive"))
      (node (ref "R30") (pin "1") (pinfunction "1_1") (pintype "passive"))
      (node (ref "VD1") (pin "1") (pinfunction "А_1") (pintype "passive"))
      (node (ref "VT3") (pin "1") (pinfunction "Б_1") (pintype "passive"))
    )
    (net (code "38") (name "Net-(VD1-К)") (class "Default")
      (node (ref "KT2") (pin "1") (pinfunction "1_1") (pintype "passive"))
      (node (ref "R28") (pin "2") (pinfunction "2_2") (pintype "passive"))
      (node (ref "VD1") (pin "2") (pinfunction "К_2") (pintype "passive"))
      (node (ref "VT1") (pin "2") (pinfunction "D_2") (pintype "passive"))
      (node (ref "XP9") (pin "1") (pintype "passive"))
    )
    (net (code "39") (name "Net-(VD2-А)") (class "Default")
      (node (ref "R29") (pin "2") (pinfunction "2_2") (pintype "passive"))
      (node (ref "VD2") (pin "1") (pinfunction "А_1") (pintype "passive"))
      (node (ref "VT1") (pin "1") (pinfunction "G_1") (pintype "passive"))
    )
    (net (code "40") (name "Net-(VD3-К)") (class "Default")
      (node (ref "C39") (pin "1") (pinfunction "1_1") (pintype "passive"))
      (node (ref "R48") (pin "2") (pinfunction "2_2") (pintype "passive"))
      (node (ref "VD3") (pin "2") (pinfunction "К_2") (pintype "passive"))
    )
    (net (code "41") (name "Net-(VT2-Б)") (class "Default")
      (node (ref "R35") (pin "1") (pinfunction "1_1") (pintype "passive"))
      (node (ref "R36") (pin "1") (pinfunction "1_1") (pintype "passive"))
      (node (ref "VT2") (pin "1") (pinfunction "Б_1") (pintype "passive"))
    )
    (net (code "42") (name "Net-(VT2-Э)") (class "Default")
      (node (ref "R31") (pin "2") (pinfunction "2_2") (pintype "passive"))
      (node (ref "VT2") (pin "3") (pinfunction "Э_3") (pintype "passive"))
    )
    (net (code "43") (name "Net-(VT3-К)") (class "Default")
      (node (ref "R32") (pin "1") (pinfunction "1_1") (pintype "passive"))
      (node (ref "VT3") (pin "2") (pinfunction "К_2") (pintype "passive"))
      (node (ref "VT4") (pin "2") (pinfunction "Б_2") (pintype "passive"))
    )
    (net (code "44") (name "Net-(VT4A-G)") (class "Default")
      (node (ref "R37") (pin "1") (pinfunction "1_1") (pintype "passive"))
      (node (ref "VT4") (pin "5") (pinfunction "G_5") (pintype "passive"))
      (node (ref "VT4") (pin "6") (pinfunction "К_6") (pintype "passive"))
    )
    (net (code "45") (name "VCC3P3") (class "Default")
      (node (ref "C34") (pin "2") (pinfunction "2_2") (pintype "passive"))
      (node (ref "C35") (pin "2") (pinfunction "2_2") (pintype "passive"))
      (node (ref "C36") (pin "2") (pinfunction "2_2") (pintype "passive"))
      (node (ref "C37") (pin "2") (pinfunction "2_2") (pintype "passive"))
      (node (ref "C44") (pin "2") (pinfunction "2_2") (pintype "passive"))
      (node (ref "C46") (pin "2") (pinfunction "2_2") (pintype "passive"))
      (node (ref "C48") (pin "2") (pinfunction "2_2") (pintype "passive"))
      (node (ref "DA3") (pin "2") (pinfunction "Out_2") (pintype "passive"))
      (node (ref "DD2") (pin "1") (pinfunction "VBAT_1") (pintype "power_in"))
      (node (ref "DD2") (pin "24") (pinfunction "VDD_24") (pintype "power_in"))
      (node (ref "DD2") (pin "36") (pinfunction "VDD_36") (pintype "power_in"))
      (node (ref "DD2") (pin "48") (pinfunction "VDD_48") (pintype "power_in"))
      (node (ref "DD2") (pin "9") (pinfunction "VDDA_9") (pintype "power_in"))
      (node (ref "HL2") (pin "1") (pinfunction "А_1") (pintype "passive"))
      (node (ref "KT7") (pin "1") (pinfunction "1_1") (pintype "passive"))
      (node (ref "R27") (pin "2") (pinfunction "2_2") (pintype "passive"))
      (node (ref "R35") (pin "2") (pinfunction "2_2") (pintype "passive"))
      (node (ref "R43") (pin "2") (pinfunction "2_2") (pintype "passive"))
      (node (ref "R56") (pin "2") (pinfunction "2_2") (pintype "passive"))
      (node (ref "VT2") (pin "2") (pinfunction "К_2") (pintype "passive"))
      (node (ref "XP8") (pin "1") (pintype "passive"))
    )
    (net (code "46") (name "VCC5P0") (class "Default")
      (node (ref "C26") (pin "2") (pinfunction "2_2") (pintype "passive"))
      (node (ref "C40") (pin "2") (pinfunction "2_2") (pintype "passive"))
      (node (ref "C41") (pin "2") (pinfunction "2_2") (pintype "passive"))
      (node (ref "C42") (pin "2") (pinfunction "2_2") (pintype "passive"))
      (node (ref "C43") (pin "2") (pinfunction "2_2") (pintype "passive"))
      (node (ref "C45") (pin "2") (pinfunction "2_2") (pintype "passive"))
      (node (ref "C47") (pin "2") (pinfunction "2_2") (pintype "passive"))
      (node (ref "DA3") (pin "3") (pinfunction "In_3") (pintype "passive"))
      (node (ref "FV1") (pin "5") (pinfunction "VBUS_5") (pintype "passive"))
      (node (ref "KT5") (pin "1") (pinfunction "1_1") (pintype "passive"))
      (node (ref "L5") (pin "2") (pinfunction "2_2") (pintype "passive"))
      (node (ref "R37") (pin "2") (pinfunction "2_2") (pintype "passive"))
      (node (ref "R54") (pin "2") (pinfunction "2_2") (pintype "passive"))
      (node (ref "VT4") (pin "3") (pinfunction "S_3") (pintype "passive"))
    )
    (net (code "47") (name "VCC5P0_USB") (class "Default")
      (node (ref "KT3") (pin "1") (pinfunction "1_1") (pintype "passive"))
      (node (ref "L4") (pin "2") (pinfunction "2_2") (pintype "passive"))
      (node (ref "R32") (pin "2") (pinfunction "2_2") (pintype "passive"))
      (node (ref "VT4") (pin "4") (pinfunction "D_4") (pintype "passive"))
    )
    (net (code "48") (name "VCCIN") (class "Default")
      (node (ref "C29") (pin "2") (pinfunction "2_2") (pintype "passive"))
      (node (ref "C30") (pin "2") (pinfunction "2_2") (pintype "passive"))
      (node (ref "C31") (pin "2") (pinfunction "2_2") (pintype "passive"))
      (node (ref "C32") (pin "2") (pinfunction "2_2") (pintype "passive"))
      (node (ref "DA2") (pin "2") (pinfunction "IN_2") (pintype "power_in"))
      (node (ref "KT4") (pin "1") (pinfunction "1_1") (pintype "passive"))
      (node (ref "R41") (pin "1") (pinfunction "1_1") (pintype "passive"))
      (node (ref "VD2") (pin "2") (pinfunction "К_2") (pintype "passive"))
      (node (ref "VD3") (pin "1") (pinfunction "А_1") (pintype "passive"))
      (node (ref "VT1") (pin "3") (pinfunction "S_3") (pintype "passive"))
    )
    (net (code "49") (name "unconnected-(DD2-PA1-Pad11)") (class "Default")
      (node (ref "DD2") (pin "11") (pinfunction "PA1_11") (pintype "bidirectional+no_connect"))
    )
    (net (code "50") (name "unconnected-(DD2-PA2-Pad12)") (class "Default")
      (node (ref "DD2") (pin "12") (pinfunction "PA2_12") (pintype "bidirectional+no_connect"))
    )
    (net (code "51") (name "unconnected-(DD2-PA3-Pad13)") (class "Default")
      (node (ref "DD2") (pin "13") (pinfunction "PA3_13") (pintype "bidirectional+no_connect"))
    )
    (net (code "52") (name "unconnected-(DD2-PA4-Pad14)") (class "Default")
      (node (ref "DD2") (pin "14") (pinfunction "PA4_14") (pintype "bidirectional+no_connect"))
    )
    (net (code "53") (name "unconnected-(DD2-PA6-Pad16)") (class "Default")
      (node (ref "DD2") (pin "16") (pinfunction "PA6_16") (pintype "bidirectional+no_connect"))
    )
    (net (code "54") (name "unconnected-(DD2-PA7-Pad17)") (class "Default")
      (node (ref "DD2") (pin "17") (pinfunction "PA7_17") (pintype "bidirectional+no_connect"))
    )
    (net (code "55") (name "unconnected-(DD2-PA8-Pad29)") (class "Default")
      (node (ref "DD2") (pin "29") (pinfunction "PA8_29") (pintype "bidirectional+no_connect"))
    )
    (net (code "56") (name "unconnected-(DD2-PA10-Pad31)") (class "Default")
      (node (ref "DD2") (pin "31") (pinfunction "PA10_31") (pintype "bidirectional+no_connect"))
    )
    (net (code "57") (name "unconnected-(DD2-PB1-Pad19)") (class "Default")
      (node (ref "DD2") (pin "19") (pinfunction "PB1_19") (pintype "bidirectional+no_connect"))
    )
    (net (code "58") (name "unconnected-(DD2-PB3-Pad39)") (class "Default")
      (node (ref "DD2") (pin "39") (pinfunction "PB3_39") (pintype "bidirectional+no_connect"))
    )
    (net (code "59") (name "unconnected-(DD2-PB4-Pad40)") (class "Default")
      (node (ref "DD2") (pin "40") (pinfunction "PB4_40") (pintype "bidirectional+no_connect"))
    )
    (net (code "60") (name "unconnected-(DD2-PB5-Pad41)") (class "Default")
      (node (ref "DD2") (pin "41") (pinfunction "PB5_41") (pintype "bidirectional+no_connect"))
    )
    (net (code "61") (name "unconnected-(DD2-PB6-Pad42)") (class "Default")
      (node (ref "DD2") (pin "42") (pinfunction "PB6_42") (pintype "bidirectional+no_connect"))
    )
    (net (code "62") (name "unconnected-(DD2-PB7-Pad43)") (class "Default")
      (node (ref "DD2") (pin "43") (pinfunction "PB7_43") (pintype "bidirectional+no_connect"))
    )
    (net (code "63") (name "unconnected-(DD2-PB8-Pad45)") (class "Default")
      (node (ref "DD2") (pin "45") (pinfunction "PB8_45") (pintype "bidirectional+no_connect"))
    )
    (net (code "64") (name "unconnected-(DD2-PB9-Pad46)") (class "Default")
      (node (ref "DD2") (pin "46") (pinfunction "PB9_46") (pintype "bidirectional+no_connect"))
    )
    (net (code "65") (name "unconnected-(DD2-PB10-Pad21)") (class "Default")
      (node (ref "DD2") (pin "21") (pinfunction "PB10_21") (pintype "bidirectional+no_connect"))
    )
    (net (code "66") (name "unconnected-(DD2-PB11-Pad22)") (class "Default")
      (node (ref "DD2") (pin "22") (pinfunction "PB11_22") (pintype "bidirectional+no_connect"))
    )
    (net (code "67") (name "unconnected-(DD2-PB15-Pad28)") (class "Default")
      (node (ref "DD2") (pin "28") (pinfunction "PB15_28") (pintype "bidirectional+no_connect"))
    )
    (net (code "68") (name "unconnected-(DD2-PC15-OSC3O-Pad4)") (class "Default")
      (node (ref "DD2") (pin "4") (pinfunction "PC15-OSC3O_4") (pintype "bidirectional+no_connect"))
    )
  )
)
